# sch_smd_1206_component_only_component.net
KiCad netlist of a schematic drawn in EAGLE
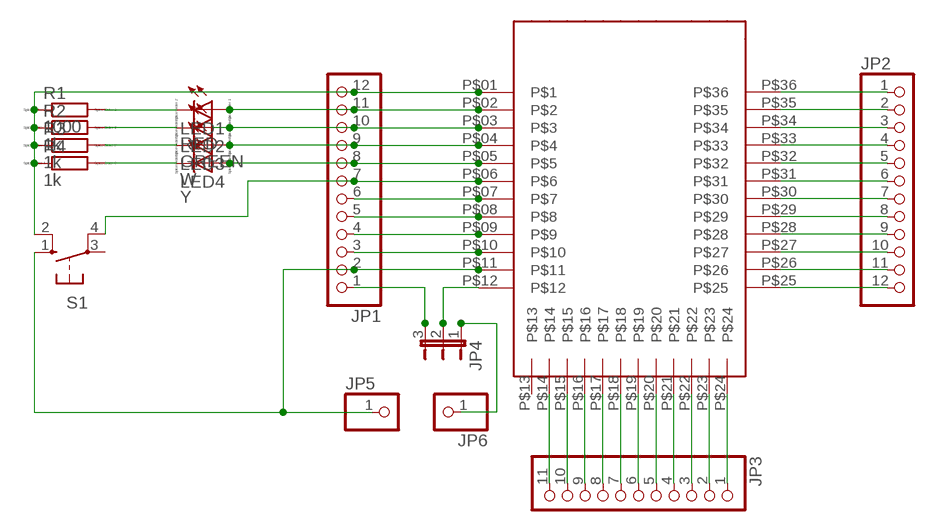
[diagram p0: schematic, sheet 1]

(export (version "E")
  (design (tool "Eeschema 10.0.6"))
  (components
    (comp (ref "JP1")
      (value "PINHD-1X12")
      (footprint "eagle-import:1X12")
      (fields (field (name "SPICEPREFIX") "X"))
      (libsource (lib "eagle-import") (part "PINHD-1X12"))
    )
    (comp (ref "JP2")
      (value "PINHD-1X12")
      (footprint "eagle-import:1X12")
      (libsource (lib "eagle-import") (part "PINHD-1X12"))
    )
    (comp (ref "JP3")
      (value "PINHD-1X11")
      (footprint "eagle-import:1X11")
      (libsource (lib "eagle-import") (part "PINHD-1X11"))
    )
    (comp (ref "JP4")
      (value "JP2E")
      (footprint "eagle-import:JP2")
      (libsource (lib "eagle-import") (part "JP2E"))
    )
    (comp (ref "JP5")
      (value "PINHD-1X1")
      (footprint "eagle-import:1X01")
      (libsource (lib "eagle-import") (part "PINHD-1X1"))
    )
    (comp (ref "JP6")
      (value "PINHD-1X1")
      (footprint "eagle-import:1X01")
      (libsource (lib "eagle-import") (part "PINHD-1X1"))
    )
    (comp (ref "LED1")
      (value "RED")
      (footprint "eagle-import:LED_1206")
      (libsource (lib "eagle-import") (part "LED_E"))
    )
    (comp (ref "LED2")
      (value "GREEN")
      (footprint "eagle-import:LED_1206")
      (libsource (lib "eagle-import") (part "LED_E"))
    )
    (comp (ref "LED3")
      (value "W")
      (footprint "eagle-import:LED_1206")
      (libsource (lib "eagle-import") (part "LED_E"))
    )
    (comp (ref "LED4")
      (value "Y")
      (footprint "eagle-import:LED_1206")
      (libsource (lib "eagle-import") (part "LED_E"))
    )
    (comp (ref "R1")
      (value "1000")
      (footprint "eagle-import:R1206")
      (libsource (lib "eagle-import") (part "RR1206"))
    )
    (comp (ref "R2")
      (value "1k")
      (footprint "eagle-import:R1206")
      (libsource (lib "eagle-import") (part "RR1206"))
    )
    (comp (ref "R3")
      (value "1k")
      (footprint "eagle-import:R1206")
      (libsource (lib "eagle-import") (part "RR1206"))
    )
    (comp (ref "R4")
      (value "1k")
      (footprint "eagle-import:R1206")
      (libsource (lib "eagle-import") (part "RR1206"))
    )
    (comp (ref "S1")
      (value "10-XX")
      (footprint "eagle-import:B3F-10XX")
      (fields (field (name "MPN") "B3F-1000"))
      (libsource (lib "eagle-import") (part "10-XX"))
    )
    (comp (ref "U$1")
      (value "HZX_MODULE")
      (footprint "eagle-import:SMD_PAD_VERSION")
      (fields (field (name "AUTHOR") "Agam"))
      (libsource (lib "eagle-import") (part "HZX_MODULE"))
    )
  )
  (nets
    (net (code "1") (name "Net-(JP1-Pad1)") (class "Default")
      (node (ref "JP1") (pin "1") (pinfunction "1_1") (pintype "passive"))
      (node (ref "JP4") (pin "3") (pinfunction "3_3") (pintype "passive"))
    )
    (net (code "2") (name "Net-(JP1-Pad3)") (class "Default")
      (node (ref "JP1") (pin "3") (pinfunction "3_3") (pintype "passive"))
      (node (ref "U$1") (pin "P$10") (pinfunction "P$10_P$10") (pintype "bidirectional"))
    )
    (net (code "3") (name "Net-(JP2-Pad1)") (class "Default")
      (node (ref "JP2") (pin "1") (pinfunction "1_1") (pintype "passive"))
      (node (ref "U$1") (pin "P$36") (pinfunction "P$36_P$36") (pintype "bidirectional"))
    )
    (net (code "4") (name "Net-(JP2-Pad2)") (class "Default")
      (node (ref "JP2") (pin "2") (pinfunction "2_2") (pintype "passive"))
      (node (ref "U$1") (pin "P$35") (pinfunction "P$35_P$35") (pintype "bidirectional"))
    )
    (net (code "5") (name "Net-(JP2-Pad3)") (class "Default")
      (node (ref "JP2") (pin "3") (pinfunction "3_3") (pintype "passive"))
      (node (ref "U$1") (pin "P$34") (pinfunction "P$34_P$34") (pintype "bidirectional"))
    )
    (net (code "6") (name "Net-(JP2-Pad4)") (class "Default")
      (node (ref "JP2") (pin "4") (pinfunction "4_4") (pintype "passive"))
      (node (ref "U$1") (pin "P$33") (pinfunction "P$33_P$33") (pintype "bidirectional"))
    )
    (net (code "7") (name "Net-(JP2-Pad5)") (class "Default")
      (node (ref "JP2") (pin "5") (pinfunction "5_5") (pintype "passive"))
      (node (ref "U$1") (pin "P$32") (pinfunction "P$32_P$32") (pintype "bidirectional"))
    )
    (net (code "8") (name "Net-(JP2-Pad6)") (class "Default")
      (node (ref "JP2") (pin "6") (pinfunction "6_6") (pintype "passive"))
      (node (ref "U$1") (pin "P$31") (pinfunction "P$31_P$31") (pintype "bidirectional"))
    )
    (net (code "9") (name "Net-(JP2-Pad7)") (class "Default")
      (node (ref "JP2") (pin "7") (pinfunction "7_7") (pintype "passive"))
      (node (ref "U$1") (pin "P$30") (pinfunction "P$30_P$30") (pintype "bidirectional"))
    )
    (net (code "10") (name "Net-(JP2-Pad8)") (class "Default")
      (node (ref "JP2") (pin "8") (pinfunction "8_8") (pintype "passive"))
      (node (ref "U$1") (pin "P$29") (pinfunction "P$29_P$29") (pintype "bidirectional"))
    )
    (net (code "11") (name "Net-(JP2-Pad9)") (class "Default")
      (node (ref "JP2") (pin "9") (pinfunction "9_9") (pintype "passive"))
      (node (ref "U$1") (pin "P$28") (pinfunction "P$28_P$28") (pintype "bidirectional"))
    )
    (net (code "12") (name "Net-(JP2-Pad10)") (class "Default")
      (node (ref "JP2") (pin "10") (pinfunction "10_10") (pintype "passive"))
      (node (ref "U$1") (pin "P$27") (pinfunction "P$27_P$27") (pintype "bidirectional"))
    )
    (net (code "13") (name "Net-(JP2-Pad11)") (class "Default")
      (node (ref "JP2") (pin "11") (pinfunction "11_11") (pintype "passive"))
      (node (ref "U$1") (pin "P$26") (pinfunction "P$26_P$26") (pintype "bidirectional"))
    )
    (net (code "14") (name "Net-(JP2-Pad12)") (class "Default")
      (node (ref "JP2") (pin "12") (pinfunction "12_12") (pintype "passive"))
      (node (ref "U$1") (pin "P$25") (pinfunction "P$25_P$25") (pintype "bidirectional"))
    )
    (net (code "15") (name "Net-(JP3-Pad1)") (class "Default")
      (node (ref "JP3") (pin "1") (pinfunction "1_1") (pintype "passive"))
      (node (ref "U$1") (pin "P$24") (pinfunction "P$24_P$24") (pintype "bidirectional"))
    )
    (net (code "16") (name "Net-(JP3-Pad2)") (class "Default")
      (node (ref "JP3") (pin "2") (pinfunction "2_2") (pintype "passive"))
      (node (ref "U$1") (pin "P$23") (pinfunction "P$23_P$23") (pintype "bidirectional"))
    )
    (net (code "17") (name "Net-(JP3-Pad3)") (class "Default")
      (node (ref "JP3") (pin "3") (pinfunction "3_3") (pintype "passive"))
      (node (ref "U$1") (pin "P$22") (pinfunction "P$22_P$22") (pintype "bidirectional"))
    )
    (net (code "18") (name "Net-(JP3-Pad4)") (class "Default")
      (node (ref "JP3") (pin "4") (pinfunction "4_4") (pintype "passive"))
      (node (ref "U$1") (pin "P$21") (pinfunction "P$21_P$21") (pintype "bidirectional"))
    )
    (net (code "19") (name "Net-(JP3-Pad5)") (class "Default")
      (node (ref "JP3") (pin "5") (pinfunction "5_5") (pintype "passive"))
      (node (ref "U$1") (pin "P$20") (pinfunction "P$20_P$20") (pintype "bidirectional"))
    )
    (net (code "20") (name "Net-(JP3-Pad6)") (class "Default")
      (node (ref "JP3") (pin "6") (pinfunction "6_6") (pintype "passive"))
      (node (ref "U$1") (pin "P$19") (pinfunction "P$19_P$19") (pintype "bidirectional"))
    )
    (net (code "21") (name "Net-(JP3-Pad7)") (class "Default")
      (node (ref "JP3") (pin "7") (pinfunction "7_7") (pintype "passive"))
      (node (ref "U$1") (pin "P$18") (pinfunction "P$18_P$18") (pintype "bidirectional"))
    )
    (net (code "22") (name "Net-(JP3-Pad8)") (class "Default")
      (node (ref "JP3") (pin "8") (pinfunction "8_8") (pintype "passive"))
      (node (ref "U$1") (pin "P$17") (pinfunction "P$17_P$17") (pintype "bidirectional"))
    )
    (net (code "23") (name "Net-(JP3-Pad9)") (class "Default")
      (node (ref "JP3") (pin "9") (pinfunction "9_9") (pintype "passive"))
      (node (ref "U$1") (pin "P$16") (pinfunction "P$16_P$16") (pintype "bidirectional"))
    )
    (net (code "24") (name "Net-(JP3-Pad10)") (class "Default")
      (node (ref "JP3") (pin "10") (pinfunction "10_10") (pintype "passive"))
      (node (ref "U$1") (pin "P$15") (pinfunction "P$15_P$15") (pintype "bidirectional"))
    )
    (net (code "25") (name "Net-(JP3-Pad11)") (class "Default")
      (node (ref "JP3") (pin "11") (pinfunction "11_11") (pintype "passive"))
      (node (ref "U$1") (pin "P$14") (pinfunction "P$14_P$14") (pintype "bidirectional"))
    )
    (net (code "26") (name "Net-(JP4-Pad1)") (class "Default")
      (node (ref "JP4") (pin "1") (pinfunction "1_1") (pintype "passive"))
      (node (ref "JP6") (pin "1") (pinfunction "1_1") (pintype "passive"))
    )
    (net (code "27") (name "Net-(JP4-Pad2)") (class "Default")
      (node (ref "JP4") (pin "2") (pinfunction "2_2") (pintype "passive"))
      (node (ref "U$1") (pin "P$12") (pinfunction "P$12_P$12") (pintype "bidirectional"))
    )
    (net (code "28") (name "Net-(LED1-PadC)") (class "Default")
      (node (ref "LED1") (pin "C") (pinfunction "C_C") (pintype "passive"))
      (node (ref "R1") (pin "2") (pinfunction "2_2") (pintype "passive"))
    )
    (net (code "29") (name "Net-(LED2-PadC)") (class "Default")
      (node (ref "LED2") (pin "C") (pinfunction "C_C") (pintype "passive"))
      (node (ref "R2") (pin "2") (pinfunction "2_2") (pintype "passive"))
    )
    (net (code "30") (name "Net-(LED3-PadC)") (class "Default")
      (node (ref "LED3") (pin "C") (pinfunction "C_C") (pintype "passive"))
      (node (ref "R3") (pin "2") (pinfunction "2_2") (pintype "passive"))
    )
    (net (code "31") (name "Net-(LED4-PadC)") (class "Default")
      (node (ref "LED4") (pin "C") (pinfunction "C_C") (pintype "passive"))
      (node (ref "R4") (pin "2") (pinfunction "2_2") (pintype "passive"))
    )
    (net (code "32") (name "Net-(S1-P1)") (class "Default")
      (node (ref "JP1") (pin "7") (pinfunction "7_7") (pintype "passive"))
      (node (ref "S1") (pin "4") (pinfunction "P1_4") (pintype "passive"))
      (node (ref "U$1") (pin "P$06") (pinfunction "P$6_P$06") (pintype "bidirectional"))
    )
    (net (code "33") (name "Net-(S1-S)") (class "Default")
      (node (ref "JP1") (pin "2") (pinfunction "2_2") (pintype "passive"))
      (node (ref "JP5") (pin "1") (pinfunction "1_1") (pintype "passive"))
      (node (ref "S1") (pin "1") (pinfunction "S_1") (pintype "passive"))
      (node (ref "U$1") (pin "P$11") (pinfunction "P$11_P$11") (pintype "bidirectional"))
    )
    (net (code "34") (name "Net-(S1-S1)") (class "Default")
      (node (ref "JP1") (pin "12") (pinfunction "12_12") (pintype "passive"))
      (node (ref "R1") (pin "1") (pinfunction "1_1") (pintype "passive"))
      (node (ref "R2") (pin "1") (pinfunction "1_1") (pintype "passive"))
      (node (ref "R3") (pin "1") (pinfunction "1_1") (pintype "passive"))
      (node (ref "R4") (pin "1") (pinfunction "1_1") (pintype "passive"))
      (node (ref "S1") (pin "2") (pinfunction "S1_2") (pintype "passive"))
      (node (ref "U$1") (pin "P$01") (pinfunction "P$1_P$01") (pintype "bidirectional"))
    )
    (net (code "35") (name "Net-(U$1-P$2)") (class "Default")
      (node (ref "JP1") (pin "11") (pinfunction "11_11") (pintype "passive"))
      (node (ref "LED1") (pin "A") (pinfunction "A_A") (pintype "passive"))
      (node (ref "U$1") (pin "P$02") (pinfunction "P$2_P$02") (pintype "bidirectional"))
    )
    (net (code "36") (name "Net-(U$1-P$3)") (class "Default")
      (node (ref "JP1") (pin "10") (pinfunction "10_10") (pintype "passive"))
      (node (ref "LED2") (pin "A") (pinfunction "A_A") (pintype "passive"))
      (node (ref "U$1") (pin "P$03") (pinfunction "P$3_P$03") (pintype "bidirectional"))
    )
    (net (code "37") (name "Net-(U$1-P$4)") (class "Default")
      (node (ref "JP1") (pin "9") (pinfunction "9_9") (pintype "passive"))
      (node (ref "LED3") (pin "A") (pinfunction "A_A") (pintype "passive"))
      (node (ref "U$1") (pin "P$04") (pinfunction "P$4_P$04") (pintype "bidirectional"))
    )
    (net (code "38") (name "Net-(U$1-P$5)") (class "Default")
      (node (ref "JP1") (pin "8") (pinfunction "8_8") (pintype "passive"))
      (node (ref "LED4") (pin "A") (pinfunction "A_A") (pintype "passive"))
      (node (ref "U$1") (pin "P$05") (pinfunction "P$5_P$05") (pintype "bidirectional"))
    )
    (net (code "39") (name "Net-(U$1-P$7)") (class "Default")
      (node (ref "JP1") (pin "6") (pinfunction "6_6") (pintype "passive"))
      (node (ref "U$1") (pin "P$07") (pinfunction "P$7_P$07") (pintype "bidirectional"))
    )
    (net (code "40") (name "Net-(U$1-P$8)") (class "Default")
      (node (ref "JP1") (pin "5") (pinfunction "5_5") (pintype "passive"))
      (node (ref "U$1") (pin "P$08") (pinfunction "P$8_P$08") (pintype "bidirectional"))
    )
    (net (code "41") (name "Net-(U$1-P$9)") (class "Default")
      (node (ref "JP1") (pin "4") (pinfunction "4_4") (pintype "passive"))
      (node (ref "U$1") (pin "P$09") (pinfunction "P$9_P$09") (pintype "bidirectional"))
    )
    (net (code "42") (name "unconnected-(S1-P-Pad3)") (class "Default")
      (node (ref "S1") (pin "3") (pinfunction "P_3") (pintype "passive"))
    )
    (net (code "43") (name "unconnected-(U$1-PadP$13)") (class "Default")
      (node (ref "U$1") (pin "P$13") (pinfunction "P$13_P$13") (pintype "bidirectional"))
    )
  )
)
